# ShutdownThree.net
KiCad netlist of a schematic drawn in EAGLE
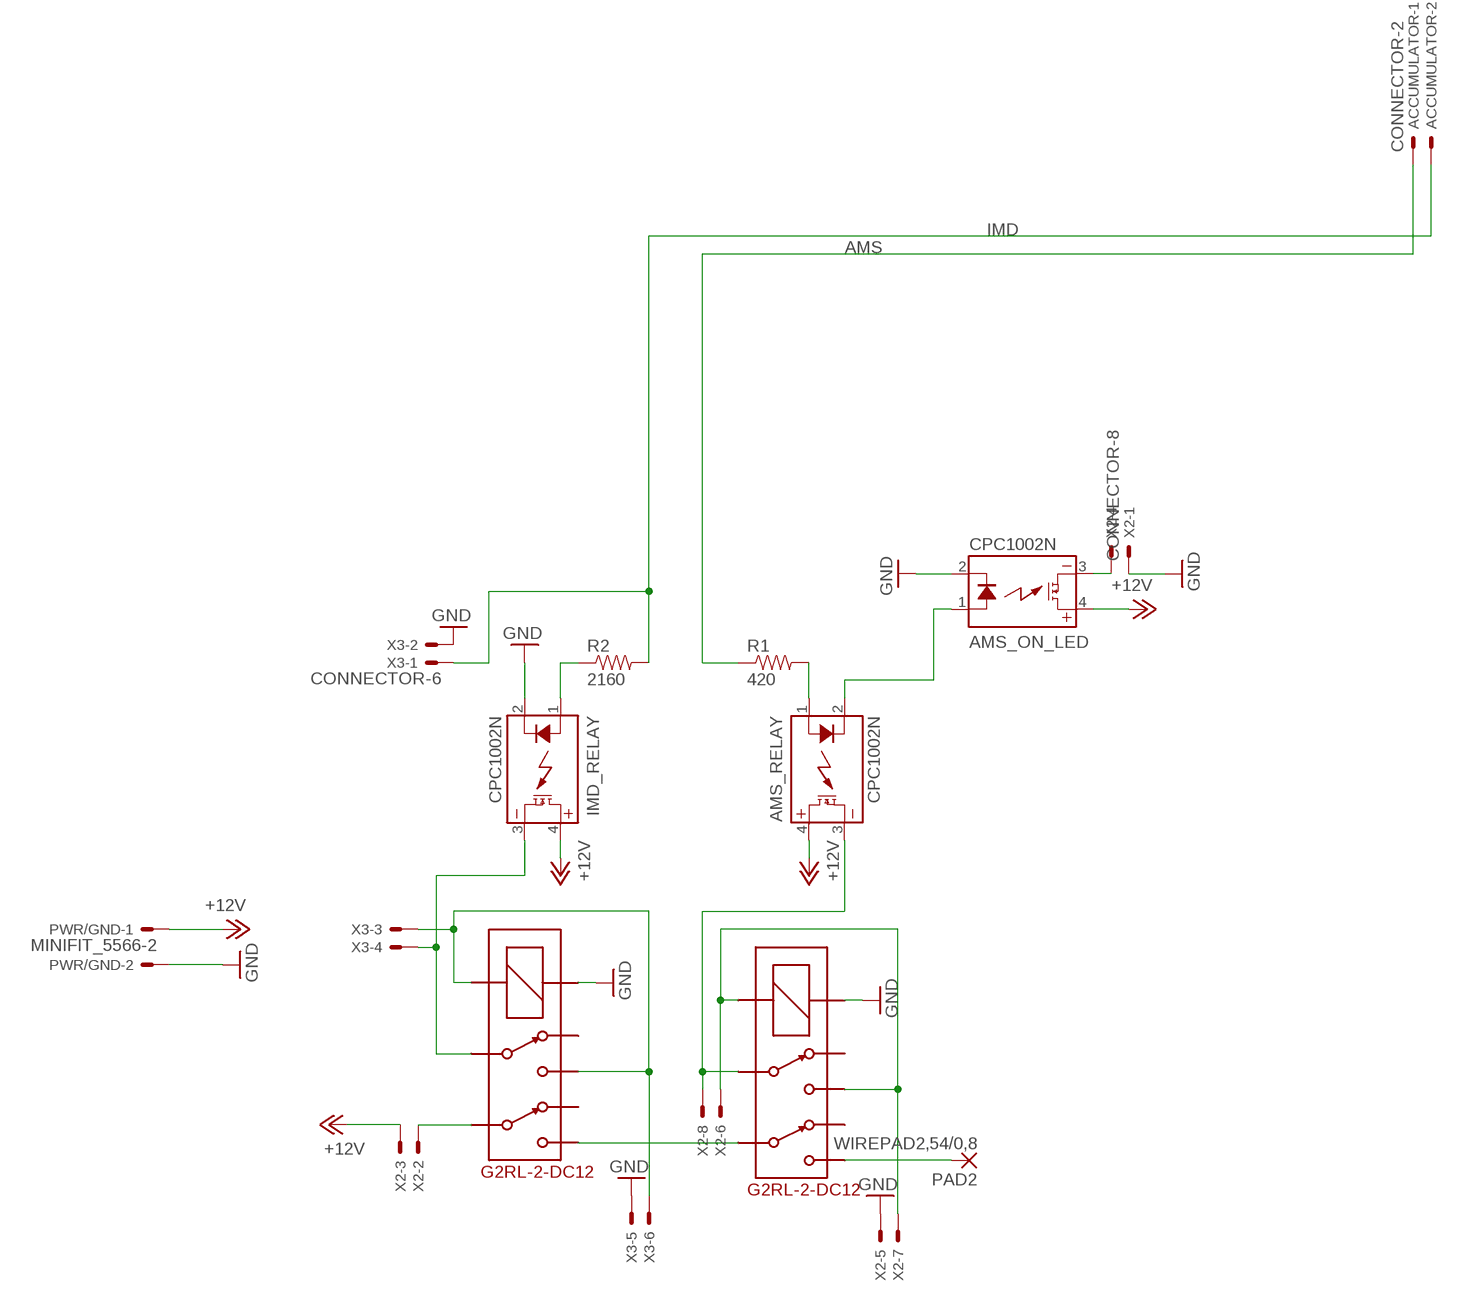
[diagram p0: schematic, sheet 1]

(export (version "E")
  (design (tool "Eeschema 10.0.6"))
  (components
    (comp (ref "ACCUMULATOR")
      (value "CONNECTOR-2")
      (footprint "eagle-import:MINIFIT_5566-2")
      (libsource (lib "eagle-import") (part "CONNECTOR-2"))
    )
    (comp (ref "AMS_ON_LED")
      (value "CPC1002N")
      (footprint "eagle-import:SOP04")
      (libsource (lib "eagle-import") (part "CPC1002N"))
    )
    (comp (ref "AMS_RELAY")
      (value "CPC1002N")
      (footprint "eagle-import:SOP04")
      (libsource (lib "eagle-import") (part "CPC1002N"))
    )
    (comp (ref "IMD")
      (value "G2RL-2-DC12")
      (footprint "eagle-import:G2RL-2")
      (libsource (lib "eagle-import") (part "G2RL-2-DC12"))
    )
    (comp (ref "IMD_RELAY")
      (value "CPC1002N")
      (footprint "eagle-import:SOP04")
      (libsource (lib "eagle-import") (part "CPC1002N"))
    )
    (comp (ref "PAD2")
      (value "WIREPAD2,54/0,8")
      (footprint "eagle-import:2,54_0,8")
      (libsource (lib "eagle-import") (part "WIREPAD2,54/0,8"))
    )
    (comp (ref "PWR/GND")
      (value "MINIFIT_5566-2")
      (footprint "eagle-import:MINIFIT_5566-2")
      (libsource (lib "eagle-import") (part "MINIFIT_5566-2"))
    )
    (comp (ref "R1")
      (value "420")
      (footprint "eagle-import:AXIAL-0.3EZ")
      (libsource (lib "eagle-import") (part "RESISTOREZ"))
    )
    (comp (ref "R2")
      (value "2160")
      (footprint "eagle-import:AXIAL-0.3EZ")
      (libsource (lib "eagle-import") (part "RESISTOREZ"))
    )
    (comp (ref "U$7")
      (value "G2RL-2-DC12")
      (footprint "eagle-import:G2RL-2")
      (libsource (lib "eagle-import") (part "G2RL-2-DC12"))
    )
    (comp (ref "X2")
      (value "CONNECTOR-8")
      (footprint "eagle-import:MINIFIT_5566-8")
      (libsource (lib "eagle-import") (part "CONNECTOR-8"))
    )
    (comp (ref "X3")
      (value "CONNECTOR-6")
      (footprint "eagle-import:MINIFIT_5566-6")
      (fields (field (name "MPN") "95566-61002"))
      (libsource (lib "eagle-import") (part "CONNECTOR-6"))
    )
  )
  (nets
    (net (code "1") (name "+12V") (class "Default")
      (node (ref "AMS_ON_LED") (pin "4") (pinfunction "DC+_4") (pintype "passive"))
      (node (ref "AMS_RELAY") (pin "4") (pinfunction "DC+_4") (pintype "passive"))
      (node (ref "IMD_RELAY") (pin "4") (pinfunction "DC+_4") (pintype "passive"))
      (node (ref "PWR/GND") (pin "1") (pinfunction "S_1") (pintype "passive"))
      (node (ref "X2") (pin "3") (pinfunction "S_3") (pintype "passive"))
    )
    (net (code "2") (name "/AMS") (class "Default")
      (node (ref "ACCUMULATOR") (pin "1") (pinfunction "S_1") (pintype "passive"))
      (node (ref "R1") (pin "P$1") (pinfunction "1_P$1") (pintype "passive"))
    )
    (net (code "3") (name "/IMD") (class "Default")
      (node (ref "ACCUMULATOR") (pin "2") (pinfunction "S_2") (pintype "passive"))
      (node (ref "R2") (pin "P$2") (pinfunction "2_P$2") (pintype "passive"))
      (node (ref "X3") (pin "1") (pinfunction "S_1") (pintype "passive"))
    )
    (net (code "4") (name "GND") (class "Default")
      (node (ref "AMS_ON_LED") (pin "2") (pinfunction "CONTROL-_2") (pintype "passive"))
      (node (ref "IMD") (pin "COIL+") (pinfunction "COIL+_COIL+") (pintype "bidirectional"))
      (node (ref "IMD_RELAY") (pin "2") (pinfunction "CONTROL-_2") (pintype "passive"))
      (node (ref "PWR/GND") (pin "2") (pinfunction "S_2") (pintype "passive"))
      (node (ref "U$7") (pin "COIL+") (pinfunction "COIL+_COIL+") (pintype "bidirectional"))
      (node (ref "X2") (pin "1") (pinfunction "S_1") (pintype "passive"))
      (node (ref "X2") (pin "5") (pinfunction "S_5") (pintype "passive"))
      (node (ref "X3") (pin "2") (pinfunction "S_2") (pintype "passive"))
      (node (ref "X3") (pin "5") (pinfunction "S_5") (pintype "passive"))
    )
    (net (code "5") (name "Net-(AMS_ON_LED-CONTROL+)") (class "Default")
      (node (ref "AMS_ON_LED") (pin "1") (pinfunction "CONTROL+_1") (pintype "passive"))
      (node (ref "AMS_RELAY") (pin "2") (pinfunction "CONTROL-_2") (pintype "passive"))
    )
    (net (code "6") (name "Net-(AMS_ON_LED-DC-)") (class "Default")
      (node (ref "AMS_ON_LED") (pin "3") (pinfunction "DC-_3") (pintype "passive"))
      (node (ref "X2") (pin "4") (pinfunction "S_4") (pintype "passive"))
    )
    (net (code "7") (name "Net-(AMS_RELAY-CONTROL+)") (class "Default")
      (node (ref "AMS_RELAY") (pin "1") (pinfunction "CONTROL+_1") (pintype "passive"))
      (node (ref "R1") (pin "P$2") (pinfunction "2_P$2") (pintype "passive"))
    )
    (net (code "8") (name "Net-(AMS_RELAY-DC-)") (class "Default")
      (node (ref "AMS_RELAY") (pin "3") (pinfunction "DC-_3") (pintype "passive"))
      (node (ref "U$7") (pin "3") (pinfunction "3_3") (pintype "bidirectional"))
      (node (ref "X2") (pin "8") (pinfunction "S_8") (pintype "passive"))
    )
    (net (code "9") (name "Net-(IMD-Pad5)") (class "Default")
      (node (ref "IMD") (pin "5") (pinfunction "5_5") (pintype "bidirectional"))
      (node (ref "U$7") (pin "6") (pinfunction "6_6") (pintype "bidirectional"))
    )
    (net (code "10") (name "Net-(IMD_RELAY-CONTROL+)") (class "Default")
      (node (ref "IMD_RELAY") (pin "1") (pinfunction "CONTROL+_1") (pintype "passive"))
      (node (ref "R2") (pin "P$1") (pinfunction "1_P$1") (pintype "passive"))
    )
    (net (code "11") (name "Net-(IMD_RELAY-DC-)") (class "Default")
      (node (ref "IMD") (pin "3") (pinfunction "3_3") (pintype "bidirectional"))
      (node (ref "IMD_RELAY") (pin "3") (pinfunction "DC-_3") (pintype "passive"))
      (node (ref "X3") (pin "4") (pinfunction "S_4") (pintype "passive"))
    )
    (net (code "12") (name "Net-(PAD2-P)") (class "Default")
      (node (ref "PAD2") (pin "1") (pinfunction "P_1") (pintype "passive"))
      (node (ref "U$7") (pin "5") (pinfunction "5_5") (pintype "bidirectional"))
    )
    (net (code "13") (name "Net-(X2B-S)") (class "Default")
      (node (ref "IMD") (pin "6") (pinfunction "6_6") (pintype "bidirectional"))
      (node (ref "X2") (pin "2") (pinfunction "S_2") (pintype "passive"))
    )
    (net (code "14") (name "Net-(X2F-S)") (class "Default")
      (node (ref "U$7") (pin "4") (pinfunction "4_4") (pintype "bidirectional"))
      (node (ref "U$7") (pin "COIL-") (pinfunction "COIL-_COIL-") (pintype "bidirectional"))
      (node (ref "X2") (pin "6") (pinfunction "S_6") (pintype "passive"))
      (node (ref "X2") (pin "7") (pinfunction "S_7") (pintype "passive"))
    )
    (net (code "15") (name "Net-(X3C-S)") (class "Default")
      (node (ref "IMD") (pin "4") (pinfunction "4_4") (pintype "bidirectional"))
      (node (ref "IMD") (pin "COIL-") (pinfunction "COIL-_COIL-") (pintype "bidirectional"))
      (node (ref "X3") (pin "3") (pinfunction "S_3") (pintype "passive"))
      (node (ref "X3") (pin "6") (pinfunction "S_6") (pintype "passive"))
    )
    (net (code "16") (name "unconnected-(IMD-Pad2)") (class "Default")
      (node (ref "IMD") (pin "2") (pinfunction "2_2") (pintype "bidirectional"))
    )
    (net (code "17") (name "unconnected-(IMD-Pad7)") (class "Default")
      (node (ref "IMD") (pin "7") (pinfunction "7_7") (pintype "bidirectional"))
    )
    (net (code "18") (name "unconnected-(U$7-Pad2)") (class "Default")
      (node (ref "U$7") (pin "2") (pinfunction "2_2") (pintype "bidirectional"))
    )
    (net (code "19") (name "unconnected-(U$7-Pad7)") (class "Default")
      (node (ref "U$7") (pin "7") (pinfunction "7_7") (pintype "bidirectional"))
    )
  )
)
